# sensor.net
KiCad netlist of a schematic drawn in Altium Designer
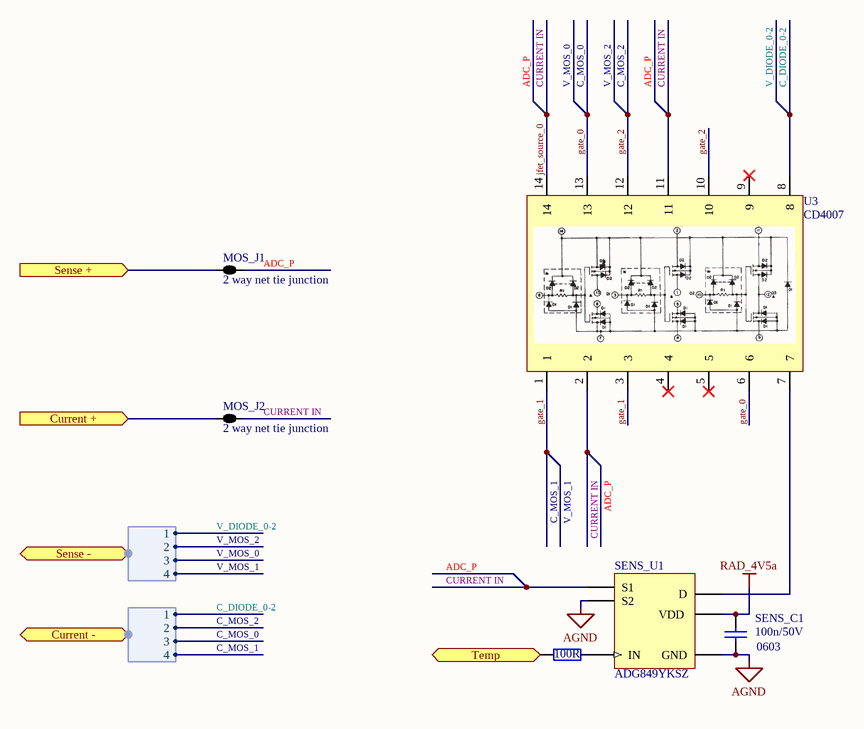
[diagram p0: sensor.SchDoc]

(export (version "E")
  (design (tool "Eeschema 10.0.6"))
  (components
    (comp (ref "MOS_J1")
      (value "2 way net tie junction")
      (footprint "2way_LP")
      (libsource (lib "NetTieLib") (part "2way"))
    )
    (comp (ref "MOS_J2")
      (value "2 way net tie junction")
      (footprint "2way_LP")
      (libsource (lib "NetTieLib") (part "2way"))
    )
    (comp (ref "SENS_1")
      (value "100R")
      (footprint "SMD_Resistor_0603")
      (libsource (lib "resistors") (part "Res"))
    )
    (comp (ref "SENS_C1")
      (value "100n/50V")
      (footprint "SMD_Capacitor_0603")
      (description "Ceramic Cap Kemet COTS 100n/50V X7R 0603")
      (fields
        (field (name "MANUFACTURER") "Kemet")
        (field (name "MANUFACTURERPARTNUMBER") "C0603T104K5RALTU")
        (field (name "PACKAGE") "0603")
      )
      (libsource (lib "capacitors") (part "Cer_C0603T104K5RALTU"))
    )
    (comp (ref "SENS_U1")
      (value "ADG849YKSZ")
      (footprint "SC70-LT6_N")
      (description "CMOS Analog switch")
      (fields
        (field (name "MANUFACTURER") "Analog Devices")
        (field (name "MANUFACTURERPARTNUMBER") "ADG849YKSZ")
      )
      (libsource (lib "microcircuits") (part "ADG849YKSZ"))
    )
    (comp (ref "U3")
      (value "CD4007")
      (footprint "TSSOP14")
      (description "CMOS Dual Complementary Pair Plus Inverter")
      (libsource (lib "transistors") (part "CD4007"))
    )
  )
  (nets
    (net (code "2") (name "/ADC_P") (class "Default")
      (node (ref "MOS_J1") (pin "2") (pinfunction "2_2") (pintype "passive"))
      (node (ref "MOS_J2") (pin "2") (pinfunction "2_2") (pintype "passive"))
      (node (ref "SENS_U1") (pin "4") (pinfunction "S1_4") (pintype "passive"))
      (node (ref "U3") (pin "11") (pinfunction "11_11") (pintype "passive"))
      (node (ref "U3") (pin "14") (pinfunction "14_14") (pintype "passive"))
      (node (ref "U3") (pin "2") (pinfunction "2_2") (pintype "passive"))
    )
    (net (code "3") (name "/C_DIODE_0-2") (class "Default")
      (node (ref "U3") (pin "8") (pinfunction "8_8") (pintype "passive"))
    )
    (net (code "4") (name "/C_MOS_0") (class "Default")
      (node (ref "U3") (pin "13") (pinfunction "13_13") (pintype "passive"))
      (node (ref "U3") (pin "6") (pinfunction "6_6") (pintype "passive"))
    )
    (net (code "5") (name "/C_MOS_1") (class "Default")
      (node (ref "U3") (pin "1") (pinfunction "1_1") (pintype "passive"))
      (node (ref "U3") (pin "3") (pinfunction "3_3") (pintype "passive"))
    )
    (net (code "6") (name "/C_MOS_2") (class "Default")
      (node (ref "U3") (pin "10") (pinfunction "10_10") (pintype "passive"))
      (node (ref "U3") (pin "12") (pinfunction "12_12") (pintype "passive"))
    )
    (net (code "7") (name "/Current +") (class "Default")
      (node (ref "MOS_J2") (pin "1") (pinfunction "1_1") (pintype "passive"))
    )
    (net (code "8") (name "/Sense +") (class "Default")
      (node (ref "MOS_J1") (pin "1") (pinfunction "1_1") (pintype "passive"))
    )
    (net (code "9") (name "/Temp") (class "Default")
      (node (ref "SENS_1") (pin "1") (pinfunction "1_1") (pintype "passive"))
    )
    (net (code "11") (name "AGND") (class "Default")
      (node (ref "SENS_C1") (pin "2") (pinfunction "2_2") (pintype "passive"))
      (node (ref "SENS_U1") (pin "3") (pinfunction "GND_3") (pintype "power_in"))
      (node (ref "SENS_U1") (pin "6") (pinfunction "S2_6") (pintype "passive"))
    )
    (net (code "12") (name "Net-(SENS_U1-D)") (class "Default")
      (node (ref "SENS_U1") (pin "5") (pinfunction "D_5") (pintype "passive"))
      (node (ref "U3") (pin "7") (pinfunction "7_7") (pintype "passive"))
    )
    (net (code "13") (name "Net-(SENS_U1-IN)") (class "Default")
      (node (ref "SENS_1") (pin "2") (pinfunction "2_2") (pintype "passive"))
      (node (ref "SENS_U1") (pin "1") (pinfunction "IN_1") (pintype "input"))
    )
    (net (code "14") (name "RAD_4V5a") (class "Default")
      (node (ref "SENS_C1") (pin "1") (pinfunction "1_1") (pintype "passive"))
      (node (ref "SENS_U1") (pin "2") (pinfunction "VDD_2") (pintype "power_in"))
    )
    (net (code "15") (name "unconnected-(U3-Pad4)") (class "Default")
      (node (ref "U3") (pin "4") (pinfunction "4_4") (pintype "passive+no_connect"))
    )
    (net (code "16") (name "unconnected-(U3-Pad5)") (class "Default")
      (node (ref "U3") (pin "5") (pinfunction "5_5") (pintype "passive+no_connect"))
    )
    (net (code "17") (name "unconnected-(U3-Pad9)") (class "Default")
      (node (ref "U3") (pin "9") (pinfunction "9_9") (pintype "passive+no_connect"))
    )
  )
)
